# WS2812-Stick_v10.net
KiCad netlist of a schematic drawn in EAGLE
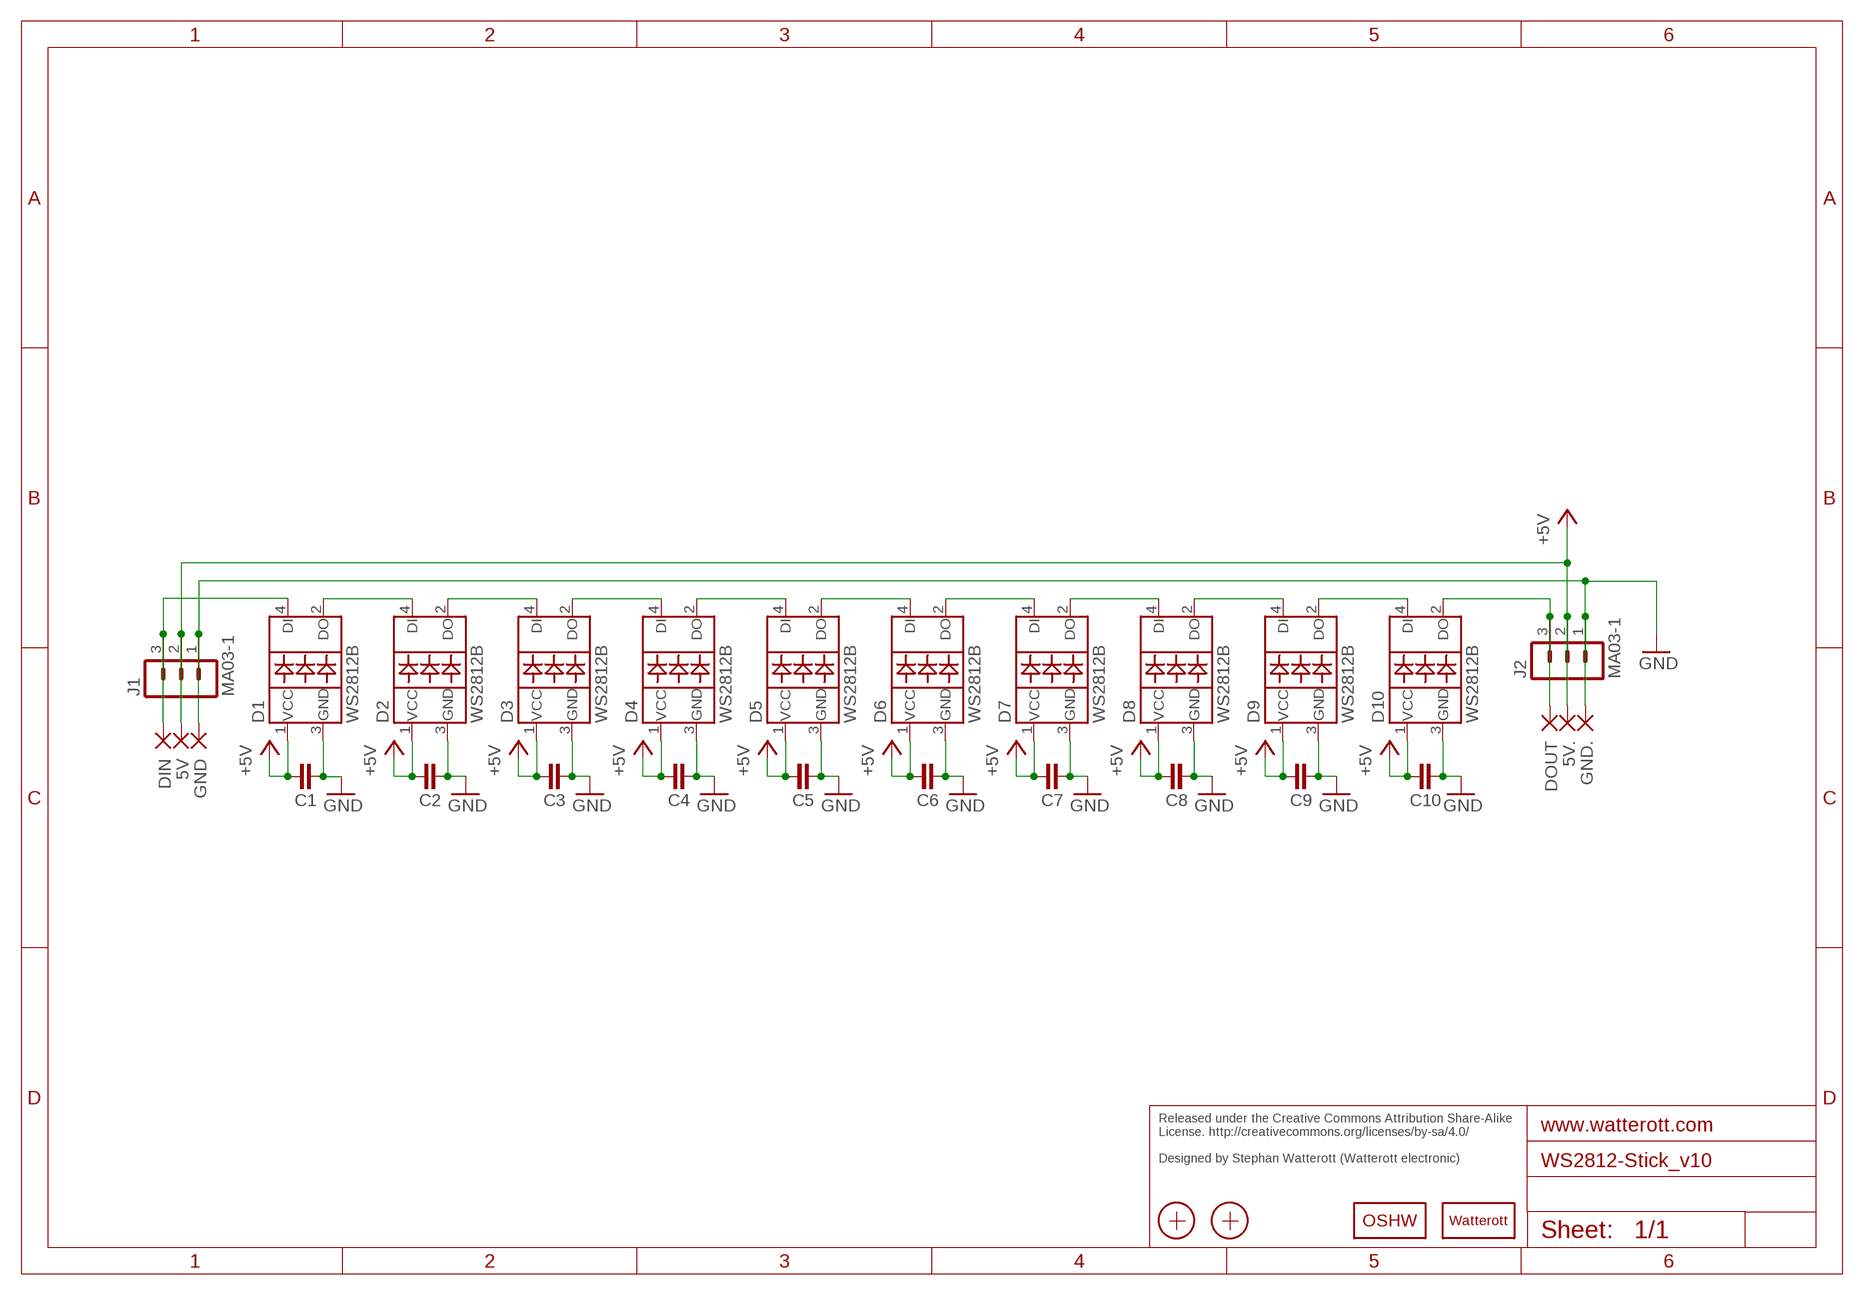
[diagram p0: schematic, sheet 1]

(export (version "E")
  (design (tool "Eeschema 10.0.6"))
  (components
    (comp (ref "5V")
      (value "SMD2")
      (footprint "eagle-import:SMD1,27-2,54")
      (libsource (lib "eagle-import") (part "SMD2"))
    )
    (comp (ref "5V.")
      (value "SMD2")
      (footprint "eagle-import:SMD1,27-2,54")
      (libsource (lib "eagle-import") (part "SMD2"))
    )
    (comp (ref "C1")
      (value "CAPACITOR-0402")
      (footprint "eagle-import:C0402")
      (libsource (lib "eagle-import") (part "CAPACITOR-0402"))
    )
    (comp (ref "C2")
      (value "CAPACITOR-0402")
      (footprint "eagle-import:C0402")
      (libsource (lib "eagle-import") (part "CAPACITOR-0402"))
    )
    (comp (ref "C3")
      (value "CAPACITOR-0402")
      (footprint "eagle-import:C0402")
      (libsource (lib "eagle-import") (part "CAPACITOR-0402"))
    )
    (comp (ref "C4")
      (value "CAPACITOR-0402")
      (footprint "eagle-import:C0402")
      (libsource (lib "eagle-import") (part "CAPACITOR-0402"))
    )
    (comp (ref "C5")
      (value "CAPACITOR-0402")
      (footprint "eagle-import:C0402")
      (libsource (lib "eagle-import") (part "CAPACITOR-0402"))
    )
    (comp (ref "C6")
      (value "CAPACITOR-0402")
      (footprint "eagle-import:C0402")
      (libsource (lib "eagle-import") (part "CAPACITOR-0402"))
    )
    (comp (ref "C7")
      (value "CAPACITOR-0402")
      (footprint "eagle-import:C0402")
      (libsource (lib "eagle-import") (part "CAPACITOR-0402"))
    )
    (comp (ref "C8")
      (value "CAPACITOR-0402")
      (footprint "eagle-import:C0402")
      (libsource (lib "eagle-import") (part "CAPACITOR-0402"))
    )
    (comp (ref "C9")
      (value "CAPACITOR-0402")
      (footprint "eagle-import:C0402")
      (libsource (lib "eagle-import") (part "CAPACITOR-0402"))
    )
    (comp (ref "C10")
      (value "CAPACITOR-0402")
      (footprint "eagle-import:C0402")
      (libsource (lib "eagle-import") (part "CAPACITOR-0402"))
    )
    (comp (ref "D1")
      (value "WS2812B")
      (footprint "eagle-import:WS2812B")
      (libsource (lib "eagle-import") (part "WS2812B"))
    )
    (comp (ref "D2")
      (value "WS2812B")
      (footprint "eagle-import:WS2812B")
      (libsource (lib "eagle-import") (part "WS2812B"))
    )
    (comp (ref "D3")
      (value "WS2812B")
      (footprint "eagle-import:WS2812B")
      (libsource (lib "eagle-import") (part "WS2812B"))
    )
    (comp (ref "D4")
      (value "WS2812B")
      (footprint "eagle-import:WS2812B")
      (libsource (lib "eagle-import") (part "WS2812B"))
    )
    (comp (ref "D5")
      (value "WS2812B")
      (footprint "eagle-import:WS2812B")
      (libsource (lib "eagle-import") (part "WS2812B"))
    )
    (comp (ref "D6")
      (value "WS2812B")
      (footprint "eagle-import:WS2812B")
      (libsource (lib "eagle-import") (part "WS2812B"))
    )
    (comp (ref "D7")
      (value "WS2812B")
      (footprint "eagle-import:WS2812B")
      (libsource (lib "eagle-import") (part "WS2812B"))
    )
    (comp (ref "D8")
      (value "WS2812B")
      (footprint "eagle-import:WS2812B")
      (libsource (lib "eagle-import") (part "WS2812B"))
    )
    (comp (ref "D9")
      (value "WS2812B")
      (footprint "eagle-import:WS2812B")
      (libsource (lib "eagle-import") (part "WS2812B"))
    )
    (comp (ref "D10")
      (value "WS2812B")
      (footprint "eagle-import:WS2812B")
      (libsource (lib "eagle-import") (part "WS2812B"))
    )
    (comp (ref "DIN")
      (value "SMD2")
      (footprint "eagle-import:SMD1,27-2,54")
      (libsource (lib "eagle-import") (part "SMD2"))
    )
    (comp (ref "DOUT")
      (value "SMD2")
      (footprint "eagle-import:SMD1,27-2,54")
      (libsource (lib "eagle-import") (part "SMD2"))
    )
    (comp (ref "GND")
      (value "SMD2")
      (footprint "eagle-import:SMD1,27-2,54")
      (libsource (lib "eagle-import") (part "SMD2"))
    )
    (comp (ref "GND.")
      (value "SMD2")
      (footprint "eagle-import:SMD1,27-2,54")
      (libsource (lib "eagle-import") (part "SMD2"))
    )
    (comp (ref "J1")
      (value "MA03-1")
      (footprint "eagle-import:MA03-1")
      (libsource (lib "eagle-import") (part "MA03-1"))
    )
    (comp (ref "J2")
      (value "MA03-1")
      (footprint "eagle-import:MA03-1")
      (libsource (lib "eagle-import") (part "MA03-1"))
    )
    (comp (ref "LOGO1")
      (value "OSHW_LOGOX0070")
      (footprint "eagle-import:OSHW_6X70")
      (libsource (lib "eagle-import") (part "OSHW_LOGOX0070"))
    )
    (comp (ref "LOGO2")
      (value "LOGO-PLACE")
      (footprint "eagle-import:LOGO_TPLACE")
      (libsource (lib "eagle-import") (part "LOGO-PLACE"))
    )
    (comp (ref "X1")
      (value "PASSER-07")
      (footprint "eagle-import:PASSER_07MM")
      (libsource (lib "eagle-import") (part "PASSER-07"))
    )
    (comp (ref "X2")
      (value "PASSER-07")
      (footprint "eagle-import:PASSER_07MM")
      (libsource (lib "eagle-import") (part "PASSER-07"))
    )
  )
  (nets
    (net (code "1") (name "+5V") (class "Default")
      (node (ref "5V") (pin "1") (pinfunction "P_1") (pintype "passive"))
      (node (ref "5V.") (pin "1") (pinfunction "P_1") (pintype "passive"))
      (node (ref "C1") (pin "2") (pinfunction "2_2") (pintype "passive"))
      (node (ref "C10") (pin "2") (pinfunction "2_2") (pintype "passive"))
      (node (ref "C2") (pin "2") (pinfunction "2_2") (pintype "passive"))
      (node (ref "C3") (pin "2") (pinfunction "2_2") (pintype "passive"))
      (node (ref "C4") (pin "2") (pinfunction "2_2") (pintype "passive"))
      (node (ref "C5") (pin "2") (pinfunction "2_2") (pintype "passive"))
      (node (ref "C6") (pin "2") (pinfunction "2_2") (pintype "passive"))
      (node (ref "C7") (pin "2") (pinfunction "2_2") (pintype "passive"))
      (node (ref "C8") (pin "2") (pinfunction "2_2") (pintype "passive"))
      (node (ref "C9") (pin "2") (pinfunction "2_2") (pintype "passive"))
      (node (ref "D1") (pin "1") (pinfunction "VCC_1") (pintype "power_in"))
      (node (ref "D10") (pin "1") (pinfunction "VCC_1") (pintype "power_in"))
      (node (ref "D2") (pin "1") (pinfunction "VCC_1") (pintype "power_in"))
      (node (ref "D3") (pin "1") (pinfunction "VCC_1") (pintype "power_in"))
      (node (ref "D4") (pin "1") (pinfunction "VCC_1") (pintype "power_in"))
      (node (ref "D5") (pin "1") (pinfunction "VCC_1") (pintype "power_in"))
      (node (ref "D6") (pin "1") (pinfunction "VCC_1") (pintype "power_in"))
      (node (ref "D7") (pin "1") (pinfunction "VCC_1") (pintype "power_in"))
      (node (ref "D8") (pin "1") (pinfunction "VCC_1") (pintype "power_in"))
      (node (ref "D9") (pin "1") (pinfunction "VCC_1") (pintype "power_in"))
      (node (ref "J1") (pin "2") (pinfunction "2_2") (pintype "passive"))
      (node (ref "J2") (pin "2") (pinfunction "2_2") (pintype "passive"))
    )
    (net (code "2") (name "GND") (class "Default")
      (node (ref "C1") (pin "1") (pinfunction "1_1") (pintype "passive"))
      (node (ref "C10") (pin "1") (pinfunction "1_1") (pintype "passive"))
      (node (ref "C2") (pin "1") (pinfunction "1_1") (pintype "passive"))
      (node (ref "C3") (pin "1") (pinfunction "1_1") (pintype "passive"))
      (node (ref "C4") (pin "1") (pinfunction "1_1") (pintype "passive"))
      (node (ref "C5") (pin "1") (pinfunction "1_1") (pintype "passive"))
      (node (ref "C6") (pin "1") (pinfunction "1_1") (pintype "passive"))
      (node (ref "C7") (pin "1") (pinfunction "1_1") (pintype "passive"))
      (node (ref "C8") (pin "1") (pinfunction "1_1") (pintype "passive"))
      (node (ref "C9") (pin "1") (pinfunction "1_1") (pintype "passive"))
      (node (ref "D1") (pin "3") (pinfunction "GND_3") (pintype "power_in"))
      (node (ref "D10") (pin "3") (pinfunction "GND_3") (pintype "power_in"))
      (node (ref "D2") (pin "3") (pinfunction "GND_3") (pintype "power_in"))
      (node (ref "D3") (pin "3") (pinfunction "GND_3") (pintype "power_in"))
      (node (ref "D4") (pin "3") (pinfunction "GND_3") (pintype "power_in"))
      (node (ref "D5") (pin "3") (pinfunction "GND_3") (pintype "power_in"))
      (node (ref "D6") (pin "3") (pinfunction "GND_3") (pintype "power_in"))
      (node (ref "D7") (pin "3") (pinfunction "GND_3") (pintype "power_in"))
      (node (ref "D8") (pin "3") (pinfunction "GND_3") (pintype "power_in"))
      (node (ref "D9") (pin "3") (pinfunction "GND_3") (pintype "power_in"))
      (node (ref "GND") (pin "1") (pinfunction "P_1") (pintype "passive"))
      (node (ref "GND.") (pin "1") (pinfunction "P_1") (pintype "passive"))
      (node (ref "J1") (pin "1") (pinfunction "1_1") (pintype "passive"))
      (node (ref "J2") (pin "1") (pinfunction "1_1") (pintype "passive"))
    )
    (net (code "3") (name "Net-(D1-DI)") (class "Default")
      (node (ref "D1") (pin "4") (pinfunction "DI_4") (pintype "bidirectional"))
      (node (ref "DIN") (pin "1") (pinfunction "P_1") (pintype "passive"))
      (node (ref "J1") (pin "3") (pinfunction "3_3") (pintype "passive"))
    )
    (net (code "4") (name "Net-(D1-DO)") (class "Default")
      (node (ref "D1") (pin "2") (pinfunction "DO_2") (pintype "bidirectional"))
      (node (ref "D2") (pin "4") (pinfunction "DI_4") (pintype "bidirectional"))
    )
    (net (code "5") (name "Net-(D2-DO)") (class "Default")
      (node (ref "D2") (pin "2") (pinfunction "DO_2") (pintype "bidirectional"))
      (node (ref "D3") (pin "4") (pinfunction "DI_4") (pintype "bidirectional"))
    )
    (net (code "6") (name "Net-(D3-DO)") (class "Default")
      (node (ref "D3") (pin "2") (pinfunction "DO_2") (pintype "bidirectional"))
      (node (ref "D4") (pin "4") (pinfunction "DI_4") (pintype "bidirectional"))
    )
    (net (code "7") (name "Net-(D4-DO)") (class "Default")
      (node (ref "D4") (pin "2") (pinfunction "DO_2") (pintype "bidirectional"))
      (node (ref "D5") (pin "4") (pinfunction "DI_4") (pintype "bidirectional"))
    )
    (net (code "8") (name "Net-(D5-DO)") (class "Default")
      (node (ref "D5") (pin "2") (pinfunction "DO_2") (pintype "bidirectional"))
      (node (ref "D6") (pin "4") (pinfunction "DI_4") (pintype "bidirectional"))
    )
    (net (code "9") (name "Net-(D6-DO)") (class "Default")
      (node (ref "D6") (pin "2") (pinfunction "DO_2") (pintype "bidirectional"))
      (node (ref "D7") (pin "4") (pinfunction "DI_4") (pintype "bidirectional"))
    )
    (net (code "10") (name "Net-(D7-DO)") (class "Default")
      (node (ref "D7") (pin "2") (pinfunction "DO_2") (pintype "bidirectional"))
      (node (ref "D8") (pin "4") (pinfunction "DI_4") (pintype "bidirectional"))
    )
    (net (code "11") (name "Net-(D8-DO)") (class "Default")
      (node (ref "D8") (pin "2") (pinfunction "DO_2") (pintype "bidirectional"))
      (node (ref "D9") (pin "4") (pinfunction "DI_4") (pintype "bidirectional"))
    )
    (net (code "12") (name "Net-(D10-DI)") (class "Default")
      (node (ref "D10") (pin "4") (pinfunction "DI_4") (pintype "bidirectional"))
      (node (ref "D9") (pin "2") (pinfunction "DO_2") (pintype "bidirectional"))
    )
    (net (code "13") (name "Net-(D10-DO)") (class "Default")
      (node (ref "D10") (pin "2") (pinfunction "DO_2") (pintype "bidirectional"))
      (node (ref "DOUT") (pin "1") (pinfunction "P_1") (pintype "passive"))
      (node (ref "J2") (pin "3") (pinfunction "3_3") (pintype "passive"))
    )
  )
)
